# GVM_Battery_Light.net
KiCad netlist of a schematic drawn in EasyEDA
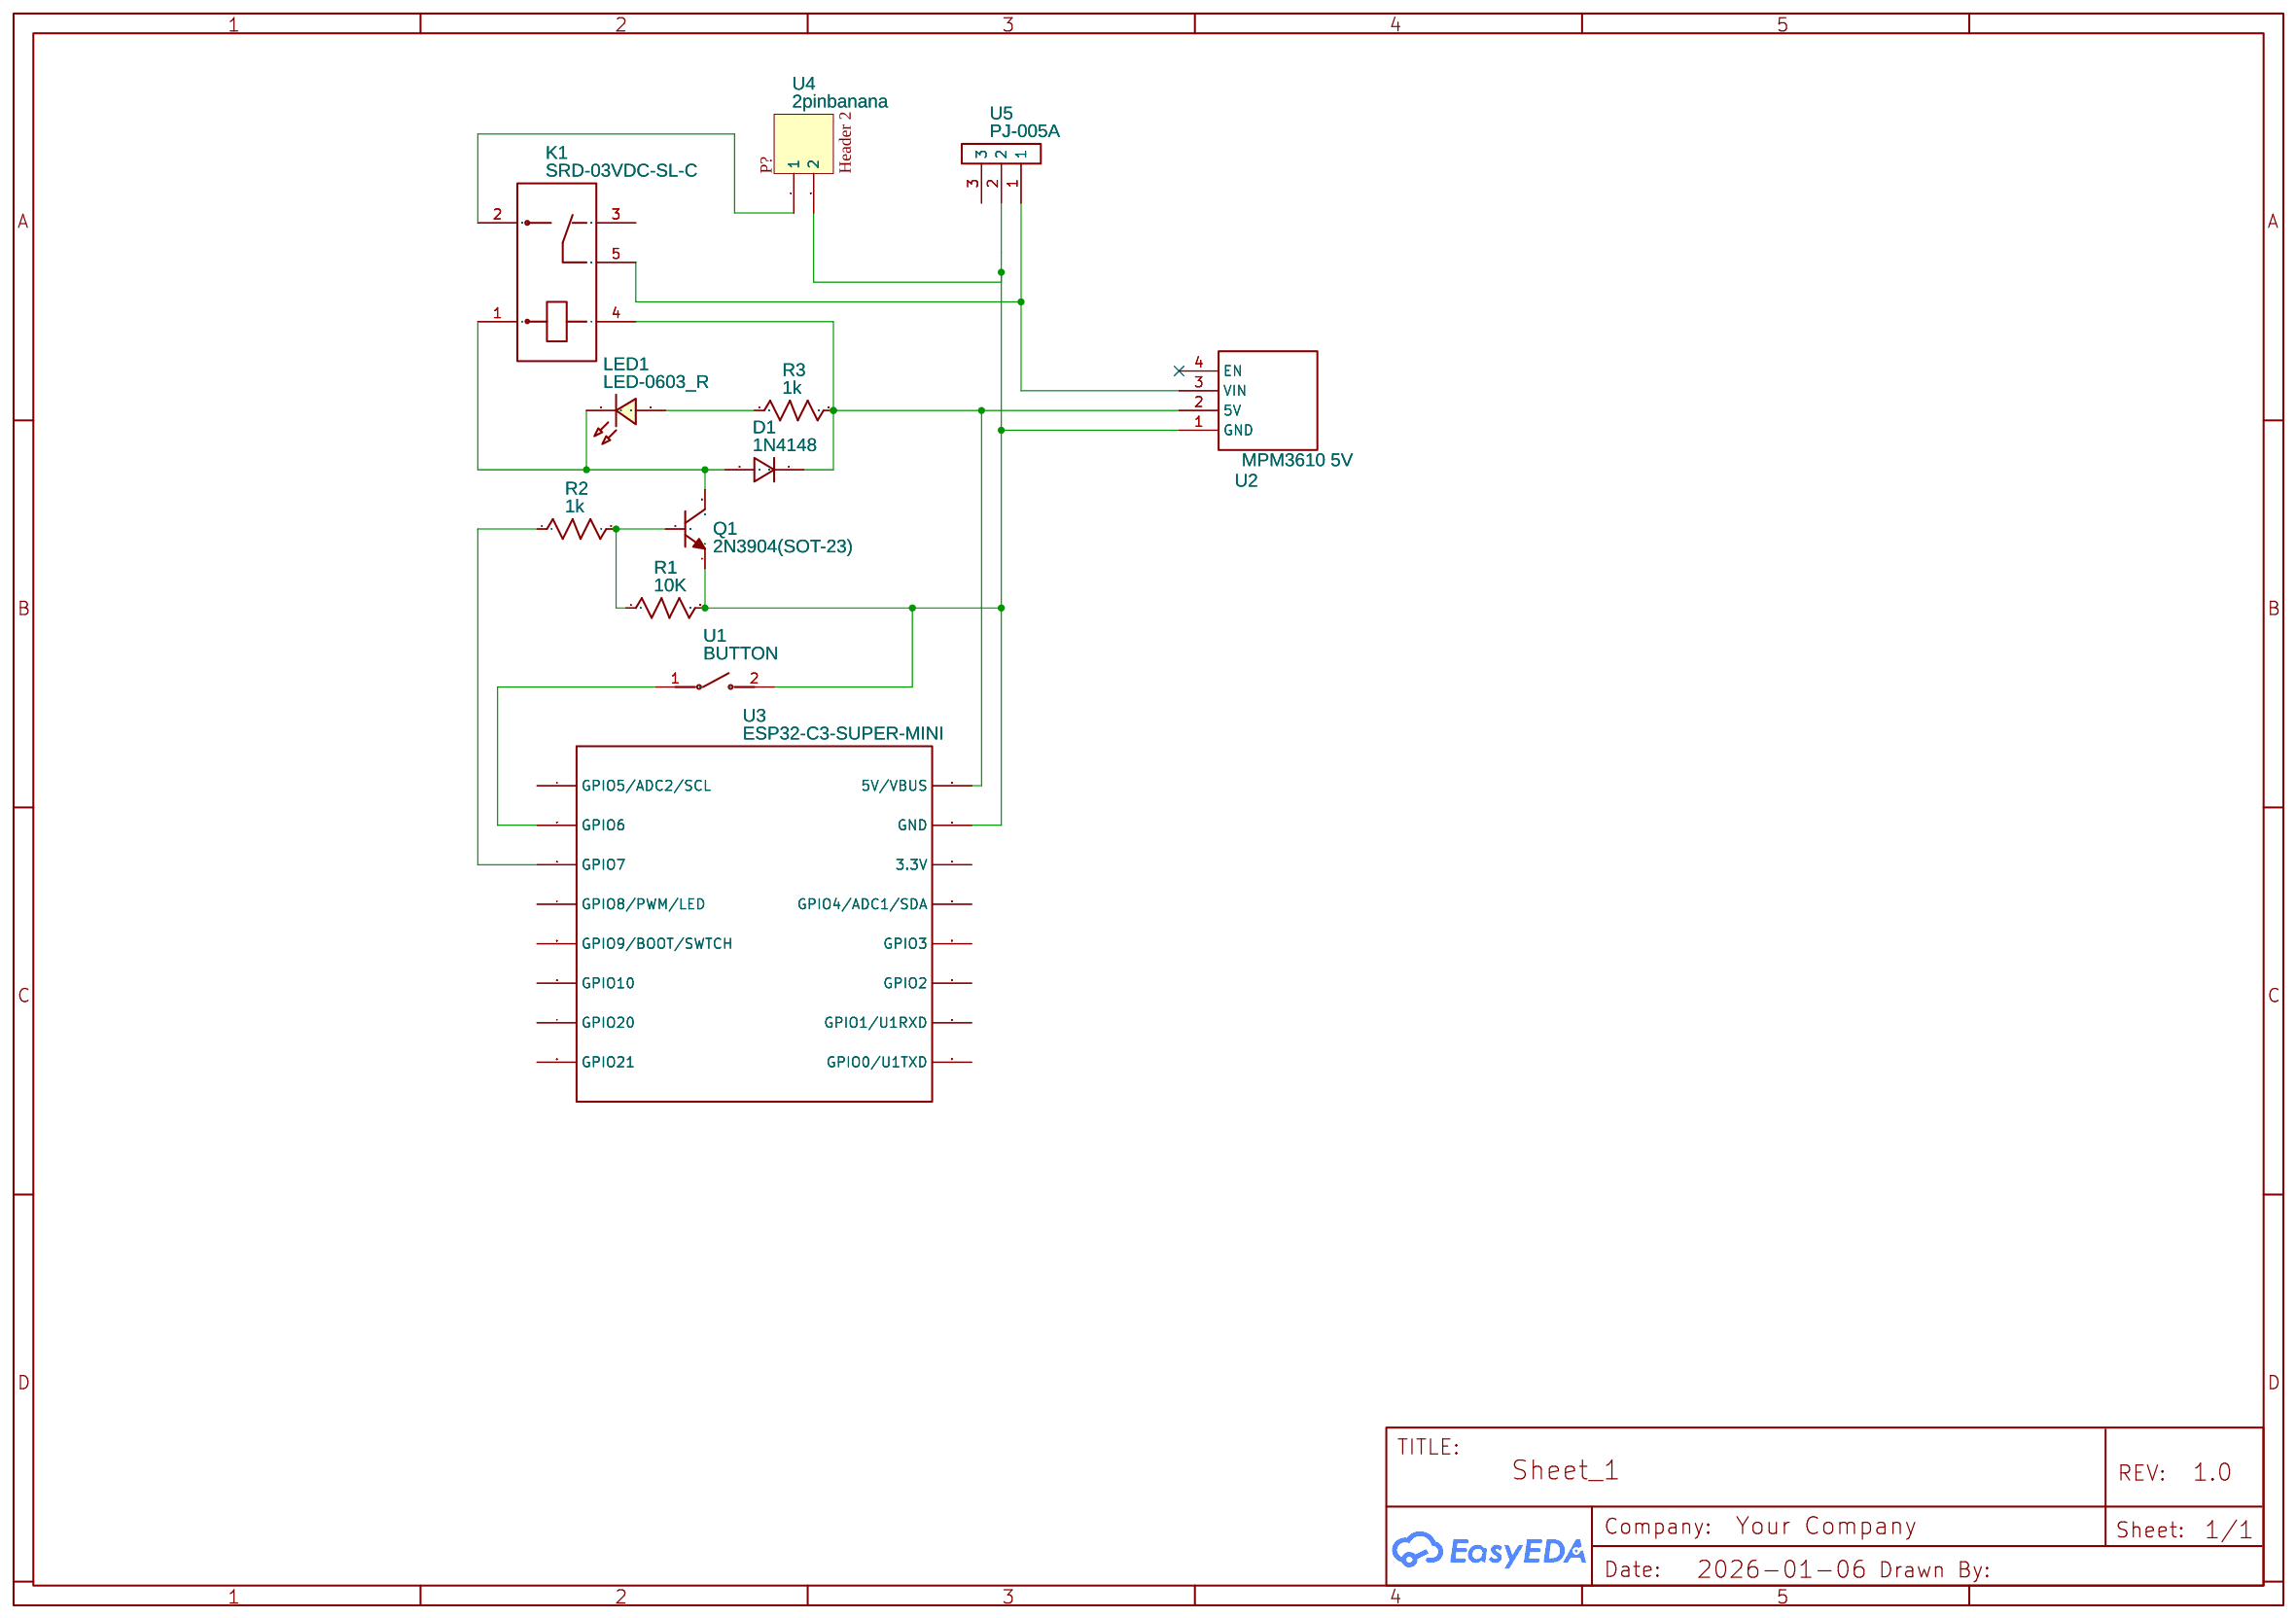
[diagram p0: schematic sheet]

(export (version "E")
  (design (tool "Eeschema 10.0.6"))
  (components
    (comp (ref "D1")
      (value "1N4148")
      (fields (field (name "Manufacturer") "STMicroelectronics"))
      (libsource (lib "") (part "1N4148"))
    )
    (comp (ref "K1")
      (value "SRD-03VDC-SL-C")
      (fields (field (name "Manufacturer") "松乐"))
      (libsource (lib "") (part "SRD-03VDC-SL-C"))
    )
    (comp (ref "LED1")
      (value "LED-0603_R")
      (fields
        (field (name "Manufacturer Part") "19-217/R6C-AL1M2VY/3T")
        (field (name "Manufacturer") "EVERLIGHT(台湾亿光)")
      )
      (libsource (lib "") (part "LED-0603_R"))
    )
    (comp (ref "Q1")
      (value "2N3904(SOT-23)")
      (fields (field (name "Manufacturer Part") "2n3904S-RTK/PS") (field (name "Manufacturer") "KEC"))
      (libsource (lib "") (part "2N3904(SOT-23)"))
    )
    (comp (ref "R1") (value "10K") (libsource (lib "") (part "R_AXIAL-0.3_US")))
    (comp (ref "R2") (value "1k") (libsource (lib "") (part "R_AXIAL-0.3_US")))
    (comp (ref "R3") (value "1k") (libsource (lib "") (part "R_AXIAL-0.3_US")))
    (comp (ref "U1") (value "BUTTON") (libsource (lib "") (part "BUTTON")))
    (comp (ref "U2")
      (value "MPM3610 5V")
      (fields (field (name "Manufacturer") "Adafruit"))
      (libsource (lib "") (part "MPM3610 5V"))
    )
    (comp (ref "U3")
      (value "ESP32-C3-SUPER-MINI")
      (fields (field (name "Manufacturer") "Maker go"))
      (libsource (lib "") (part "ESP32-C3-SUPER-MINI"))
    )
    (comp (ref "U4") (value "2pinbanana") (libsource (lib "") (part "2pinbanana")))
    (comp (ref "U5") (value "PJ-005A") (libsource (lib "") (part "PJ-005A")))
  )
  (nets
    (net (code "1") (name "Net-(K1-Pad2)") (class "Default")
      (node (ref "K1") (pin "2") (pinfunction "2_2") (pintype "unspecified"))
      (node (ref "U4") (pin "1") (pinfunction "1_1") (pintype "unspecified"))
    )
    (net (code "2") (name "Net-(LED1-Pad1)") (class "Default")
      (node (ref "LED1") (pin "1") (pinfunction "1_1") (pintype "unspecified"))
      (node (ref "R3") (pin "1") (pinfunction "1_1") (pintype "unspecified"))
    )
    (net (code "3") (name "Net-(Q1-B)") (class "Default")
      (node (ref "Q1") (pin "2") (pinfunction "B_2") (pintype "input"))
      (node (ref "R1") (pin "1") (pinfunction "1_1") (pintype "unspecified"))
      (node (ref "R2") (pin "2") (pinfunction "2_2") (pintype "unspecified"))
    )
    (net (code "4") (name "Net-(Q1-C)") (class "Default")
      (node (ref "D1") (pin "2") (pinfunction "2_2") (pintype "unspecified"))
      (node (ref "K1") (pin "1") (pinfunction "1_1") (pintype "unspecified"))
      (node (ref "LED1") (pin "2") (pinfunction "2_2") (pintype "unspecified"))
      (node (ref "Q1") (pin "3") (pinfunction "C_3") (pintype "input"))
    )
    (net (code "5") (name "Net-(Q1-E)") (class "Default")
      (node (ref "Q1") (pin "1") (pinfunction "E_1") (pintype "input"))
      (node (ref "R1") (pin "2") (pinfunction "2_2") (pintype "unspecified"))
      (node (ref "U1") (pin "2") (pinfunction "2_2") (pintype "unspecified"))
      (node (ref "U2") (pin "1") (pinfunction "GND_1") (pintype "unspecified"))
      (node (ref "U3") (pin "15") (pinfunction "GND_15") (pintype "unspecified"))
      (node (ref "U4") (pin "2") (pinfunction "2_2") (pintype "unspecified"))
      (node (ref "U5") (pin "2") (pinfunction "2_2") (pintype "unspecified"))
    )
    (net (code "6") (name "Net-(U2-5V)") (class "Default")
      (node (ref "D1") (pin "1") (pinfunction "1_1") (pintype "unspecified"))
      (node (ref "K1") (pin "4") (pinfunction "4_4") (pintype "unspecified"))
      (node (ref "R3") (pin "2") (pinfunction "2_2") (pintype "unspecified"))
      (node (ref "U2") (pin "2") (pinfunction "5V_2") (pintype "unspecified"))
      (node (ref "U3") (pin "16") (pinfunction "5V/VBUS_16") (pintype "unspecified"))
    )
    (net (code "7") (name "Net-(U2-VIN)") (class "Default")
      (node (ref "K1") (pin "5") (pinfunction "5_5") (pintype "unspecified"))
      (node (ref "U2") (pin "3") (pinfunction "VIN_3") (pintype "unspecified"))
      (node (ref "U5") (pin "1") (pinfunction "1_1") (pintype "unspecified"))
    )
    (net (code "8") (name "Net-(U3-GPIO6)") (class "Default")
      (node (ref "U1") (pin "1") (pinfunction "1_1") (pintype "unspecified"))
      (node (ref "U3") (pin "2") (pinfunction "GPIO6_2") (pintype "unspecified"))
    )
    (net (code "9") (name "Net-(U3-GPIO7)") (class "Default")
      (node (ref "R2") (pin "1") (pinfunction "1_1") (pintype "unspecified"))
      (node (ref "U3") (pin "3") (pinfunction "GPIO7_3") (pintype "unspecified"))
    )
    (net (code "10") (name "unconnected-(K1-Pad3)") (class "Default")
      (node (ref "K1") (pin "3") (pinfunction "3_3") (pintype "unspecified"))
    )
    (net (code "11") (name "unconnected-(U2-EN-Pad4)") (class "Default")
      (node (ref "U2") (pin "4") (pinfunction "EN_4") (pintype "unspecified+no_connect"))
    )
    (net (code "12") (name "unconnected-(U3-3.3V-Pad14)") (class "Default")
      (node (ref "U3") (pin "14") (pinfunction "3.3V_14") (pintype "unspecified"))
    )
    (net (code "13") (name "unconnected-(U3-GPIO0{slash}U1TXD-Pad9)") (class "Default")
      (node (ref "U3") (pin "9") (pinfunction "GPIO0/U1TXD_9") (pintype "unspecified"))
    )
    (net (code "14") (name "unconnected-(U3-GPIO1{slash}U1RXD-Pad10)") (class "Default")
      (node (ref "U3") (pin "10") (pinfunction "GPIO1/U1RXD_10") (pintype "unspecified"))
    )
    (net (code "15") (name "unconnected-(U3-GPIO2-Pad11)") (class "Default")
      (node (ref "U3") (pin "11") (pinfunction "GPIO2_11") (pintype "unspecified"))
    )
    (net (code "16") (name "unconnected-(U3-GPIO3-Pad12)") (class "Default")
      (node (ref "U3") (pin "12") (pinfunction "GPIO3_12") (pintype "unspecified"))
    )
    (net (code "17") (name "unconnected-(U3-GPIO4{slash}ADC1{slash}SDA-Pad13)") (class "Default")
      (node (ref "U3") (pin "13") (pinfunction "GPIO4/ADC1/SDA_13") (pintype "unspecified"))
    )
    (net (code "18") (name "unconnected-(U3-GPIO5{slash}ADC2{slash}SCL-Pad1)") (class "Default")
      (node (ref "U3") (pin "1") (pinfunction "GPIO5/ADC2/SCL_1") (pintype "unspecified"))
    )
    (net (code "19") (name "unconnected-(U3-GPIO8{slash}PWM{slash}LED-Pad4)") (class "Default")
      (node (ref "U3") (pin "4") (pinfunction "GPIO8/PWM/LED_4") (pintype "unspecified"))
    )
    (net (code "20") (name "unconnected-(U3-GPIO9{slash}BOOT{slash}SWTCH-Pad5)") (class "Default")
      (node (ref "U3") (pin "5") (pinfunction "GPIO9/BOOT/SWTCH_5") (pintype "unspecified"))
    )
    (net (code "21") (name "unconnected-(U3-GPIO10-Pad6)") (class "Default")
      (node (ref "U3") (pin "6") (pinfunction "GPIO10_6") (pintype "unspecified"))
    )
    (net (code "22") (name "unconnected-(U3-GPIO20-Pad7)") (class "Default")
      (node (ref "U3") (pin "7") (pinfunction "GPIO20_7") (pintype "unspecified"))
    )
    (net (code "23") (name "unconnected-(U3-GPIO21-Pad8)") (class "Default")
      (node (ref "U3") (pin "8") (pinfunction "GPIO21_8") (pintype "unspecified"))
    )
    (net (code "24") (name "unconnected-(U5-Pad3)") (class "Default")
      (node (ref "U5") (pin "3") (pinfunction "3_3") (pintype "unspecified"))
    )
  )
)
